# 4_Sensors.net
KiCad netlist of a schematic drawn in Altium Designer
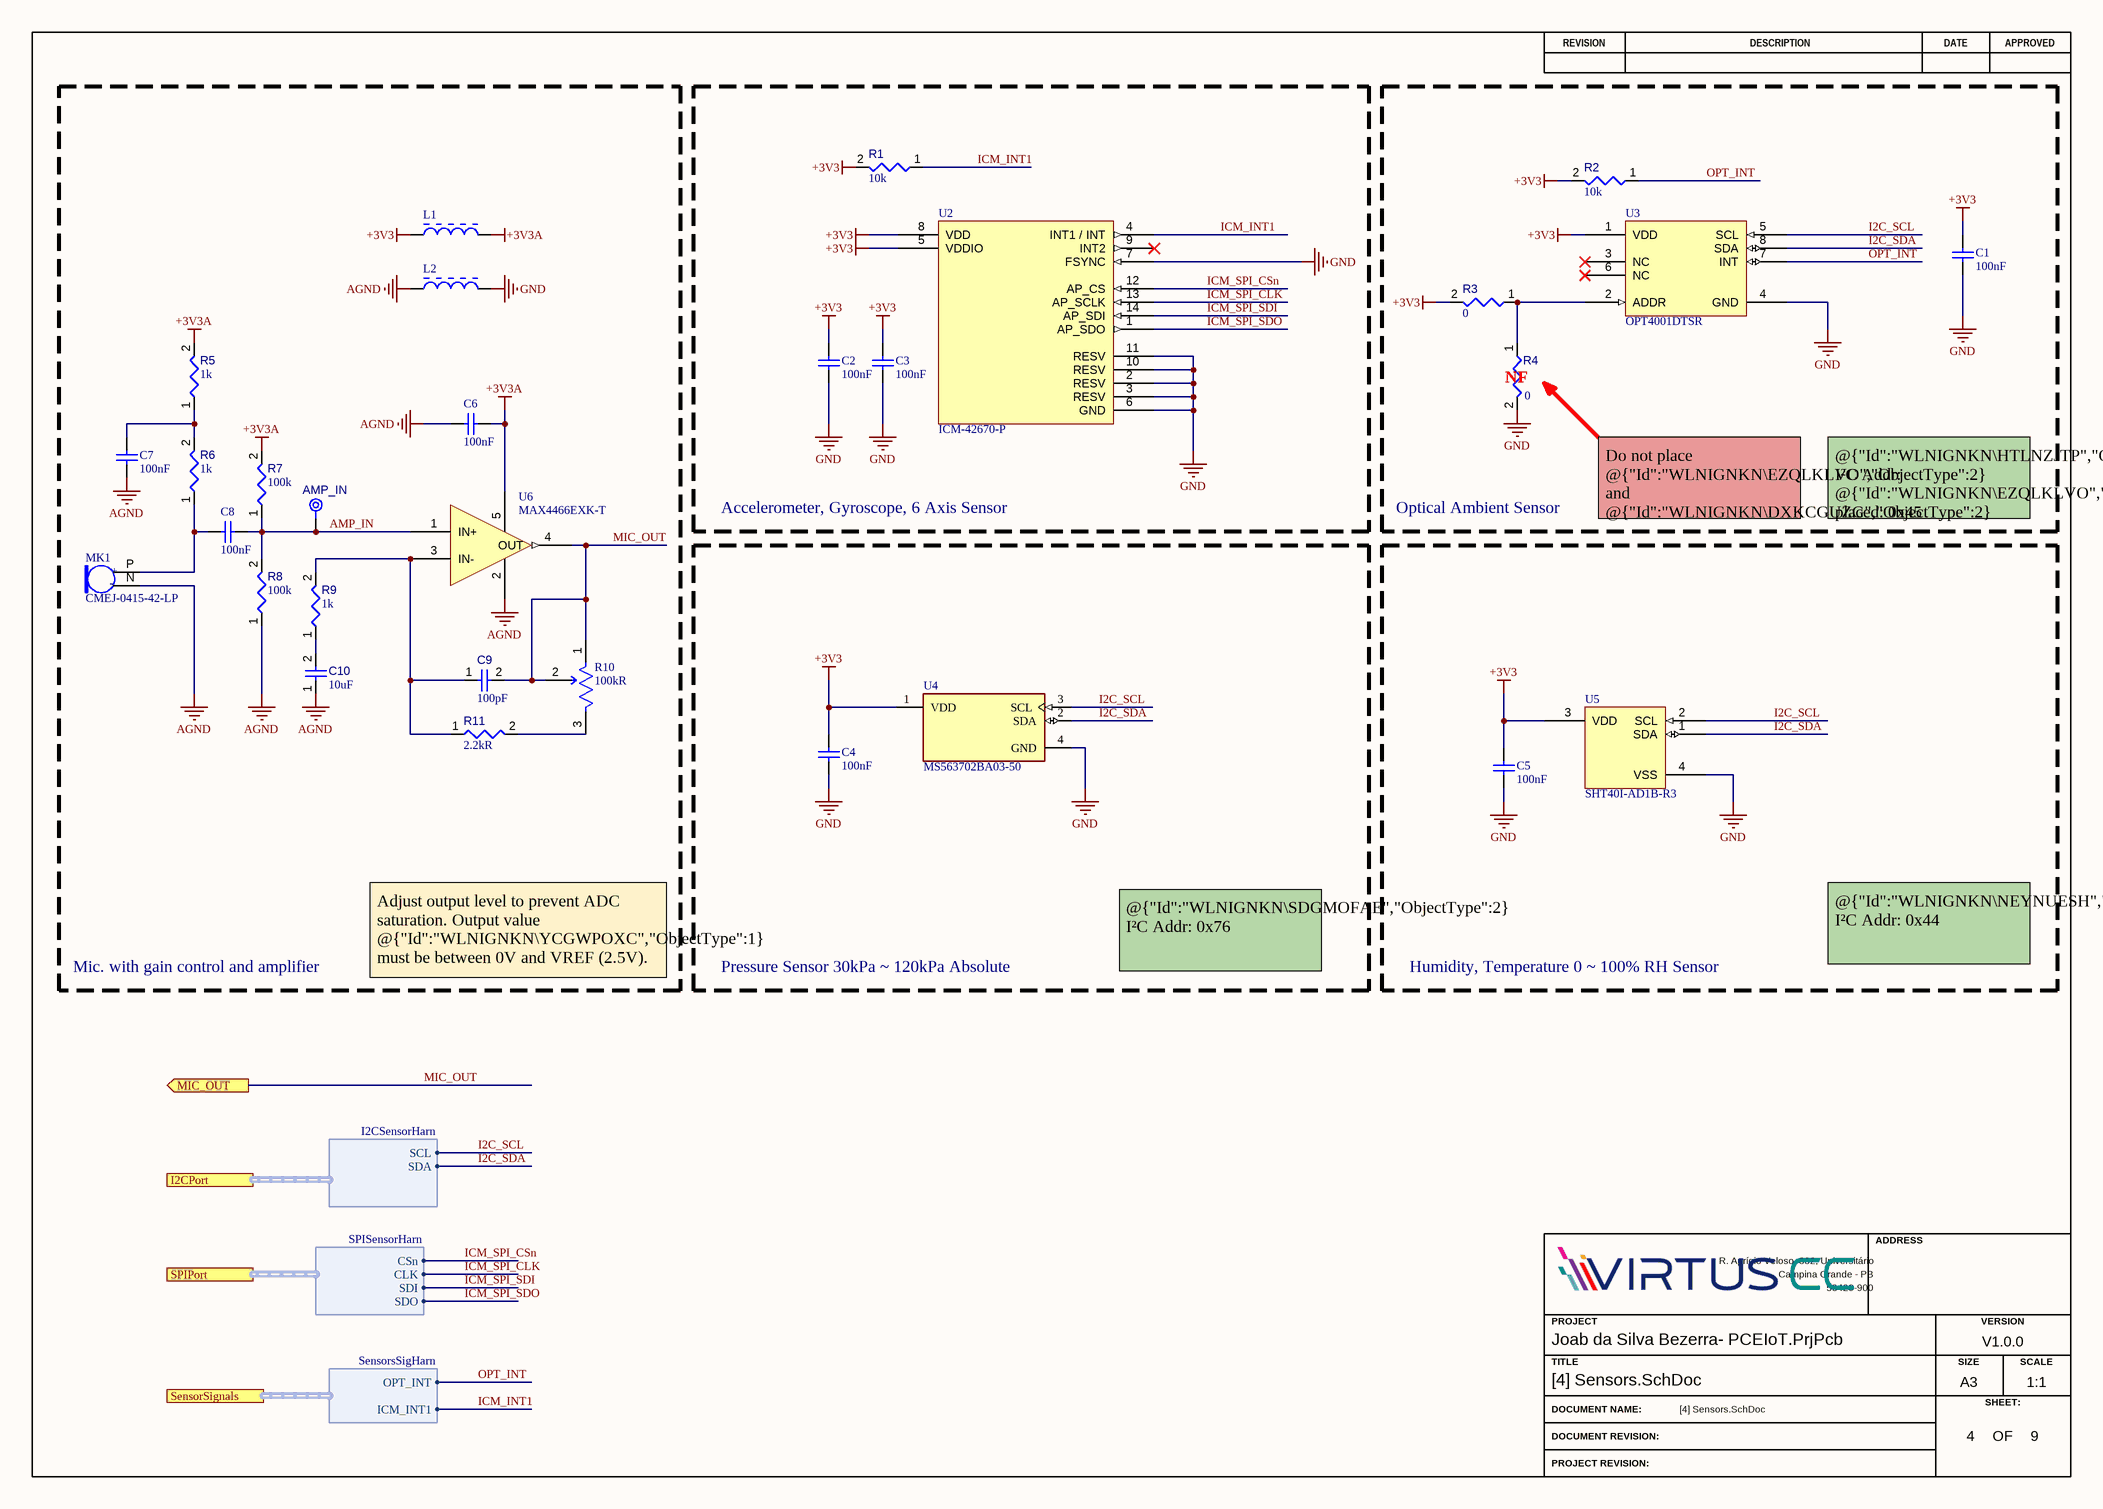
[diagram p0: [4] Sensors.SchDoc]

(export (version "E")
  (design (tool "Eeschema 10.0.6"))
  (components
    (comp (ref "AMP_IN")
      (value "TPAD6R")
      (footprint "TP06R")
      (description "0.6mm round")
      (libsource (lib "UFCG - Universidade Federal de Campina Grande") (part "CMP-001-0001-4"))
    )
    (comp (ref "C1")
      (value "100nF")
      (footprint "CAPC0603(1608)100_L")
      (description "Multilayer Ceramic Capacitor, 0.1 uF, 16 V, ± 20%, X7R, 0603 [1608 Metric]")
      (fields (field (name "TOLERANCE") "20%") (field (name "Comment") "VJ0603Y104MXJCW1BC"))
      (libsource (lib "UFCG - Universidade Federal de Campina Grande") (part "CAP"))
    )
    (comp (ref "C2")
      (value "100nF")
      (footprint "CAPC0603(1608)100_L")
      (description "Multilayer Ceramic Capacitor, 0.1 uF, 16 V, ± 20%, X7R, 0603 [1608 Metric]")
      (fields (field (name "TOLERANCE") "20%") (field (name "Comment") "VJ0603Y104MXJCW1BC"))
      (libsource (lib "UFCG - Universidade Federal de Campina Grande") (part "CAP"))
    )
    (comp (ref "C3")
      (value "100nF")
      (footprint "CAPC0603(1608)100_L")
      (description "Multilayer Ceramic Capacitor, 0.1 uF, 16 V, ± 20%, X7R, 0603 [1608 Metric]")
      (fields (field (name "TOLERANCE") "20%") (field (name "Comment") "VJ0603Y104MXJCW1BC"))
      (libsource (lib "UFCG - Universidade Federal de Campina Grande") (part "CAP"))
    )
    (comp (ref "C4")
      (value "100nF")
      (footprint "CAPC0603(1608)100_L")
      (description "Multilayer Ceramic Capacitor, 0.1 uF, 16 V, ± 20%, X7R, 0603 [1608 Metric]")
      (fields (field (name "TOLERANCE") "20%") (field (name "Comment") "VJ0603Y104MXJCW1BC"))
      (libsource (lib "UFCG - Universidade Federal de Campina Grande") (part "CAP"))
    )
    (comp (ref "C5")
      (value "100nF")
      (footprint "CAPC0603(1608)100_L")
      (description "Multilayer Ceramic Capacitor, 0.1 uF, 16 V, ± 20%, X7R, 0603 [1608 Metric]")
      (fields (field (name "TOLERANCE") "20%") (field (name "Comment") "VJ0603Y104MXJCW1BC"))
      (libsource (lib "UFCG - Universidade Federal de Campina Grande") (part "CAP"))
    )
    (comp (ref "C6")
      (value "100nF")
      (footprint "CAPC0603(1608)100_L")
      (description "Multilayer Ceramic Capacitor, 0.1 uF, 16 V, ± 20%, X7R, 0603 [1608 Metric]")
      (fields (field (name "TOLERANCE") "20%") (field (name "Comment") "VJ0603Y104MXJCW1BC"))
      (libsource (lib "UFCG - Universidade Federal de Campina Grande") (part "CAP"))
    )
    (comp (ref "C7")
      (value "100nF")
      (footprint "CAPC0603(1608)100_L")
      (description "Multilayer Ceramic Capacitor, 0.1 uF, 16 V, ± 20%, X7R, 0603 [1608 Metric]")
      (fields (field (name "TOLERANCE") "20%") (field (name "Comment") "VJ0603Y104MXJCW1BC"))
      (libsource (lib "UFCG - Universidade Federal de Campina Grande") (part "CAP"))
    )
    (comp (ref "C8")
      (value "100nF")
      (footprint "CAPC0603(1608)100_L")
      (description "Multilayer Ceramic Capacitor, 0.1 uF, 16 V, ± 20%, X7R, 0603 [1608 Metric]")
      (fields (field (name "TOLERANCE") "20%") (field (name "Comment") "VJ0603Y104MXJCW1BC"))
      (libsource (lib "UFCG - Universidade Federal de Campina Grande") (part "CAP"))
    )
    (comp (ref "C9")
      (value "100pF")
      (footprint "CAPC0603(1608)100_L")
      (description "Multilayer Ceramic Capacitor, 100 pF, 50 V, ï¿½ 10%, C0G (NP0), 0603 [1608 Metric]")
      (fields (field (name "TOLERANCE") "10%") (field (name "Comment") "C0603C101K5GACTU"))
      (libsource (lib "UFCG - Universidade Federal de Campina Grande") (part "CAP-NP-2"))
    )
    (comp (ref "C10")
      (value "10uF")
      (footprint "CAPC0603(1608)100_L")
      (description "Multilayer Ceramic Capacitor, 10 uF, 6.3 V, ± 20%, X5R, 0603 [1608 Metric]")
      (fields (field (name "TOLERANCE") "20%") (field (name "Comment") "GRM188R60J106ME47D"))
      (libsource (lib "UFCG - Universidade Federal de Campina Grande") (part "CAP-NP-2"))
    )
    (comp (ref "L1")
      (value "BLM21PG331SN1D")
      (footprint "INDC2013X105X50ML20T20")
      (fields (field (name "MANUFACTURER") "Murata") (field (name "TOLERANCE") "25%"))
      (libsource (lib "UFCG - Universidade Federal de Campina Grande") (part "IND-FB-2"))
    )
    (comp (ref "L2")
      (value "BLM21PG331SN1D")
      (footprint "INDC2013X105X50ML20T20")
      (fields (field (name "MANUFACTURER") "Murata") (field (name "TOLERANCE") "25%"))
      (libsource (lib "UFCG - Universidade Federal de Campina Grande") (part "IND-FB-2"))
    )
    (comp (ref "MK1")
      (value "CMEJ-0415-42-LP")
      (footprint "MIC_CMEJ-0415-42-LP")
      (description "4.0 mm, Omnidirectional, PCB Mount, 2.0 Vdc, Elecret Condenser Microphone")
      (fields (field (name "MF") "{'manufacturer': u'CUI'}"))
      (libsource (lib "UFCG - Universidade Federal de Campina Grande") (part "CMEJ-0415-42-LP"))
    )
    (comp (ref "R1")
      (value "10k")
      (footprint "RESC0603(1608)_L")
      (description "Chip Resistor, 10 KOhm, +/- 1%, 01 W, -55 to 155 degC, 0603 (1608 Metric)")
      (fields (field (name "POWER") "100mW") (field (name "TOLERANCE") "1%"))
      (libsource (lib "UFCG - Universidade Federal de Campina Grande") (part "RES-2"))
    )
    (comp (ref "R2")
      (value "10k")
      (footprint "RESC0603(1608)_L")
      (description "Chip Resistor, 10 KOhm, +/- 1%, 01 W, -55 to 155 degC, 0603 (1608 Metric)")
      (fields (field (name "POWER") "100mW") (field (name "TOLERANCE") "1%"))
      (libsource (lib "UFCG - Universidade Federal de Campina Grande") (part "RES-2"))
    )
    (comp (ref "R3")
      (value "0")
      (footprint "RESC0603(1608)_L")
      (description "Chip Resistor, 0 Ohm, 0.1 W, -55 to 155 degC, 0603 (1608 Metric)")
      (fields (field (name "TOLERANCE") "5%") (field (name "POWER") "100mW"))
      (libsource (lib "UFCG - Universidade Federal de Campina Grande") (part "RES-2"))
    )
    (comp (ref "R4")
      (value "0")
      (footprint "RESC0603(1608)_L")
      (description "Chip Resistor, 0 Ohm, 0.1 W, -55 to 155 degC, 0603 (1608 Metric)")
      (fields (field (name "TOLERANCE") "5%") (field (name "POWER") "100mW"))
      (libsource (lib "UFCG - Universidade Federal de Campina Grande") (part "RES-2"))
    )
    (comp (ref "R5")
      (value "1k")
      (footprint "RESC0603(1608)_L")
      (description "Chip Resistor, 1 KOhm, +/-1%, 0.1 W, -55 to 155 degC, 0603 (1608 Metric)")
      (fields (field (name "POWER") "100mW") (field (name "TOLERANCE") "1%"))
      (libsource (lib "UFCG - Universidade Federal de Campina Grande") (part "RES-2"))
    )
    (comp (ref "R6")
      (value "1k")
      (footprint "RESC0603(1608)_L")
      (description "Chip Resistor, 1 KOhm, +/-1%, 0.1 W, -55 to 155 degC, 0603 (1608 Metric)")
      (fields (field (name "POWER") "100mW") (field (name "TOLERANCE") "1%"))
      (libsource (lib "UFCG - Universidade Federal de Campina Grande") (part "RES-2"))
    )
    (comp (ref "R7")
      (value "100k")
      (footprint "RESC0603(1608)_L")
      (description "Chip Resistor, 100 KOhm, +/- 1%, 0.1 W, -55 to 155 degC, 0603 (1608 Metric)")
      (fields (field (name "TOLERANCE") "1%") (field (name "POWER") "100mW"))
      (libsource (lib "UFCG - Universidade Federal de Campina Grande") (part "RES-2"))
    )
    (comp (ref "R8")
      (value "100k")
      (footprint "RESC0603(1608)_L")
      (description "Chip Resistor, 100 KOhm, +/- 1%, 0.1 W, -55 to 155 degC, 0603 (1608 Metric)")
      (fields (field (name "TOLERANCE") "1%") (field (name "POWER") "100mW"))
      (libsource (lib "UFCG - Universidade Federal de Campina Grande") (part "RES-2"))
    )
    (comp (ref "R9")
      (value "1k")
      (footprint "RESC0603(1608)_L")
      (description "Chip Resistor, 1 KOhm, +/-1%, 0.1 W, -55 to 155 degC, 0603 (1608 Metric)")
      (fields (field (name "POWER") "100mW") (field (name "TOLERANCE") "1%"))
      (libsource (lib "UFCG - Universidade Federal de Campina Grande") (part "RES-2"))
    )
    (comp (ref "R10")
      (value "100kR")
      (footprint "FP-TC33X-2-MFG")
      (description "Cermet trimmer potentiometer, 100 kΩ, 0.1 W, SMD, on top, TC33X-2-104E")
      (fields (field (name "TOLERANCE") "25%") (field (name "Comment") "TC33X-2-104E"))
      (libsource (lib "UFCG - Universidade Federal de Campina Grande") (part "13357d81287629c2fd191d242cfa50c"))
    )
    (comp (ref "R11")
      (value "2.2kR")
      (footprint "RESC0603(1608)_L")
      (description "SMD Chip Resistor, 2.2 kOhm, ± 1%, 100 mW, 0603 [1608 Metric], Thick Film, General Purpose")
      (fields (field (name "TOLERANCE") "1%") (field (name "Comment") "CRCW06032K20FKEA"))
      (libsource (lib "UFCG - Universidade Federal de Campina Grande") (part "RES-2"))
    )
    (comp (ref "U2")
      (value "ICM-42670-P")
      (footprint "QFN50P300X250X81-14N")
      (description "Mems Module, 1.71-3.6 V, Lga-14 Rohs Compliant: Yes")
      (libsource (lib "UFCG - Universidade Federal de Campina Grande") (part "ICM-42670-P"))
    )
    (comp (ref "U3")
      (value "OPT4001DTSR")
      (footprint "SON50P130X60-8N")
      (description "High-speed high-precision digital ambient light sensor (ALS) 8-SOT-5X3 -40 to 85")
      (libsource (lib "UFCG - Universidade Federal de Campina Grande") (part "New symbol 1"))
    )
    (comp (ref "U4")
      (value "MS563702BA03-50")
      (footprint "FP-MS563702BA03-50-MFG")
      (description "Pressure Sensor, Barometric, 300 mbar, 1200 mbar, QFN, 8, -40 C")
      (libsource (lib "UFCG - Universidade Federal de Campina Grande") (part "74709a9a55dd6d6ee219151e6d8b12f"))
    )
    (comp (ref "U5")
      (value "SHT40I-AD1B-R3")
      (footprint "QFN80P150X150X55-4N")
      (description "Humidity And Temperature Sensor")
      (libsource (lib "UFCG - Universidade Federal de Campina Grande") (part "SHT40I-AD1B-R3"))
    )
    (comp (ref "U6")
      (value "MAX4466EXK-T")
      (footprint "SOT65P200X110-5N")
      (description "Audio Amp Microphone 1-CH Mono Class-AB 5-Pin SC-70 T/R")
      (libsource (lib "UFCG - Universidade Federal de Campina Grande") (part "MAX4466EXK-T"))
    )
  )
  (nets
    (net (code "4") (name "+3V3") (class "Default")
      (node (ref "C1") (pin "1") (pinfunction "1_1") (pintype "passive"))
      (node (ref "C2") (pin "1") (pinfunction "1_1") (pintype "passive"))
      (node (ref "C3") (pin "1") (pinfunction "1_1") (pintype "passive"))
      (node (ref "C4") (pin "2") (pinfunction "2_2") (pintype "passive"))
      (node (ref "C5") (pin "2") (pinfunction "2_2") (pintype "passive"))
      (node (ref "L1") (pin "1") (pinfunction "1_1") (pintype "passive"))
      (node (ref "R1") (pin "2") (pinfunction "2_2") (pintype "passive"))
      (node (ref "R2") (pin "2") (pinfunction "2_2") (pintype "passive"))
      (node (ref "R3") (pin "2") (pinfunction "2_2") (pintype "passive"))
      (node (ref "U2") (pin "5") (pinfunction "VDDIO_5") (pintype "power_in"))
      (node (ref "U2") (pin "8") (pinfunction "VDD_8") (pintype "power_in"))
      (node (ref "U3") (pin "1") (pinfunction "VDD_1") (pintype "power_in"))
      (node (ref "U4") (pin "1") (pinfunction "VDD_1") (pintype "power_in"))
      (node (ref "U5") (pin "3") (pinfunction "VDD_3") (pintype "power_in"))
    )
    (net (code "5") (name "+3V3A") (class "Default")
      (node (ref "C6") (pin "2") (pinfunction "2_2") (pintype "passive"))
      (node (ref "L1") (pin "2") (pinfunction "2_2") (pintype "passive"))
      (node (ref "R5") (pin "2") (pinfunction "2_2") (pintype "passive"))
      (node (ref "R7") (pin "2") (pinfunction "2_2") (pintype "passive"))
      (node (ref "U6") (pin "5") (pinfunction "VCC_5") (pintype "power_in"))
    )
    (net (code "6") (name "/AMP_IN") (class "Default")
      (node (ref "AMP_IN") (pin "1") (pinfunction "TP_1") (pintype "passive"))
      (node (ref "C8") (pin "2") (pinfunction "2_2") (pintype "passive"))
      (node (ref "R7") (pin "1") (pinfunction "1_1") (pintype "passive"))
      (node (ref "R8") (pin "2") (pinfunction "2_2") (pintype "passive"))
      (node (ref "U6") (pin "1") (pinfunction "IN+_1") (pintype "passive"))
    )
    (net (code "7") (name "/I2C_SCL") (class "Default")
      (node (ref "U3") (pin "5") (pinfunction "SCL_5") (pintype "input"))
      (node (ref "U4") (pin "3") (pinfunction "SCL_3") (pintype "input"))
      (node (ref "U5") (pin "2") (pinfunction "SCL_2") (pintype "input"))
    )
    (net (code "8") (name "/I2C_SDA") (class "Default")
      (node (ref "U3") (pin "8") (pinfunction "SDA_8") (pintype "bidirectional"))
      (node (ref "U4") (pin "2") (pinfunction "SDA_2") (pintype "bidirectional"))
      (node (ref "U5") (pin "1") (pinfunction "SDA_1") (pintype "bidirectional"))
    )
    (net (code "9") (name "/ICM_INT1") (class "Default")
      (node (ref "R1") (pin "1") (pinfunction "1_1") (pintype "passive"))
      (node (ref "U2") (pin "4") (pinfunction "INT1_/_INT_4") (pintype "output"))
    )
    (net (code "10") (name "/ICM_SPI_CLK") (class "Default")
      (node (ref "U2") (pin "13") (pinfunction "AP_SCLK_13") (pintype "input"))
    )
    (net (code "11") (name "/ICM_SPI_CSn") (class "Default")
      (node (ref "U2") (pin "12") (pinfunction "AP_CS_12") (pintype "input"))
    )
    (net (code "12") (name "/ICM_SPI_SDI") (class "Default")
      (node (ref "U2") (pin "14") (pinfunction "AP_SDI_14") (pintype "input"))
    )
    (net (code "13") (name "/ICM_SPI_SDO") (class "Default")
      (node (ref "U2") (pin "1") (pinfunction "AP_SDO_1") (pintype "output"))
    )
    (net (code "14") (name "/MIC_OUT") (class "Default")
      (node (ref "C9") (pin "2") (pinfunction "2_2") (pintype "passive"))
      (node (ref "R10") (pin "1") (pinfunction "CCW_1") (pintype "passive"))
      (node (ref "R10") (pin "2") (pinfunction "WIPER_2") (pintype "passive"))
      (node (ref "U6") (pin "4") (pinfunction "OUT_4") (pintype "output"))
    )
    (net (code "15") (name "/OPT_INT") (class "Default")
      (node (ref "R2") (pin "1") (pinfunction "1_1") (pintype "passive"))
      (node (ref "U3") (pin "7") (pinfunction "INT_7") (pintype "bidirectional"))
    )
    (net (code "19") (name "AGND") (class "Default")
      (node (ref "C10") (pin "1") (pinfunction "1_1") (pintype "passive"))
      (node (ref "C6") (pin "1") (pinfunction "1_1") (pintype "passive"))
      (node (ref "C7") (pin "1") (pinfunction "1_1") (pintype "passive"))
      (node (ref "L2") (pin "1") (pinfunction "1_1") (pintype "passive"))
      (node (ref "MK1") (pin "N") (pinfunction "GND_N") (pintype "passive"))
      (node (ref "R8") (pin "1") (pinfunction "1_1") (pintype "passive"))
      (node (ref "U6") (pin "2") (pinfunction "GND_2") (pintype "power_in"))
    )
    (net (code "20") (name "GND") (class "Default")
      (node (ref "C1") (pin "2") (pinfunction "2_2") (pintype "passive"))
      (node (ref "C2") (pin "2") (pinfunction "2_2") (pintype "passive"))
      (node (ref "C3") (pin "2") (pinfunction "2_2") (pintype "passive"))
      (node (ref "C4") (pin "1") (pinfunction "1_1") (pintype "passive"))
      (node (ref "C5") (pin "1") (pinfunction "1_1") (pintype "passive"))
      (node (ref "L2") (pin "2") (pinfunction "2_2") (pintype "passive"))
      (node (ref "R4") (pin "2") (pinfunction "2_2") (pintype "passive"))
      (node (ref "U2") (pin "10") (pinfunction "RESV_10") (pintype "passive"))
      (node (ref "U2") (pin "11") (pinfunction "RESV_11") (pintype "passive"))
      (node (ref "U2") (pin "2") (pinfunction "RESV_2") (pintype "passive"))
      (node (ref "U2") (pin "3") (pinfunction "RESV_3") (pintype "passive"))
      (node (ref "U2") (pin "6") (pinfunction "GND_6") (pintype "power_in"))
      (node (ref "U2") (pin "7") (pinfunction "FSYNC_7") (pintype "input"))
      (node (ref "U3") (pin "4") (pinfunction "GND_4") (pintype "power_in"))
      (node (ref "U4") (pin "4") (pinfunction "GND_4") (pintype "power_in"))
      (node (ref "U5") (pin "4") (pinfunction "VSS_4") (pintype "power_in"))
    )
    (net (code "21") (name "Net-(C7-Pad2)") (class "Default")
      (node (ref "C7") (pin "2") (pinfunction "2_2") (pintype "passive"))
      (node (ref "R5") (pin "1") (pinfunction "1_1") (pintype "passive"))
      (node (ref "R6") (pin "2") (pinfunction "2_2") (pintype "passive"))
    )
    (net (code "22") (name "Net-(C10-Pad2)") (class "Default")
      (node (ref "C10") (pin "2") (pinfunction "2_2") (pintype "passive"))
      (node (ref "R9") (pin "1") (pinfunction "1_1") (pintype "passive"))
    )
    (net (code "23") (name "Net-(MK1-OUTPUT)") (class "Default")
      (node (ref "C8") (pin "1") (pinfunction "1_1") (pintype "passive"))
      (node (ref "MK1") (pin "P") (pinfunction "OUTPUT_P") (pintype "passive"))
      (node (ref "R6") (pin "1") (pinfunction "1_1") (pintype "passive"))
    )
    (net (code "24") (name "Net-(R10-CW)") (class "Default")
      (node (ref "R10") (pin "3") (pinfunction "CW_3") (pintype "passive"))
      (node (ref "R11") (pin "2") (pinfunction "2_2") (pintype "passive"))
    )
    (net (code "25") (name "Net-(U3-ADDR)") (class "Default")
      (node (ref "R3") (pin "1") (pinfunction "1_1") (pintype "passive"))
      (node (ref "R4") (pin "1") (pinfunction "1_1") (pintype "passive"))
      (node (ref "U3") (pin "2") (pinfunction "ADDR_2") (pintype "input"))
    )
    (net (code "26") (name "Net-(U6-IN-)") (class "Default")
      (node (ref "C9") (pin "1") (pinfunction "1_1") (pintype "passive"))
      (node (ref "R11") (pin "1") (pinfunction "1_1") (pintype "passive"))
      (node (ref "R9") (pin "2") (pinfunction "2_2") (pintype "passive"))
      (node (ref "U6") (pin "3") (pinfunction "IN-_3") (pintype "passive"))
    )
    (net (code "27") (name "unconnected-(U2-INT2-Pad9)") (class "Default")
      (node (ref "U2") (pin "9") (pinfunction "INT2_9") (pintype "output+no_connect"))
    )
    (net (code "28") (name "unconnected-(U3-NC-Pad3)") (class "Default")
      (node (ref "U3") (pin "3") (pinfunction "NC_3") (pintype "passive+no_connect"))
    )
    (net (code "29") (name "unconnected-(U3-NC-Pad6)") (class "Default")
      (node (ref "U3") (pin "6") (pinfunction "NC_6") (pintype "passive+no_connect"))
    )
  )
)
